# Quad_ESC_controller.net
KiCad netlist of a schematic drawn in EAGLE
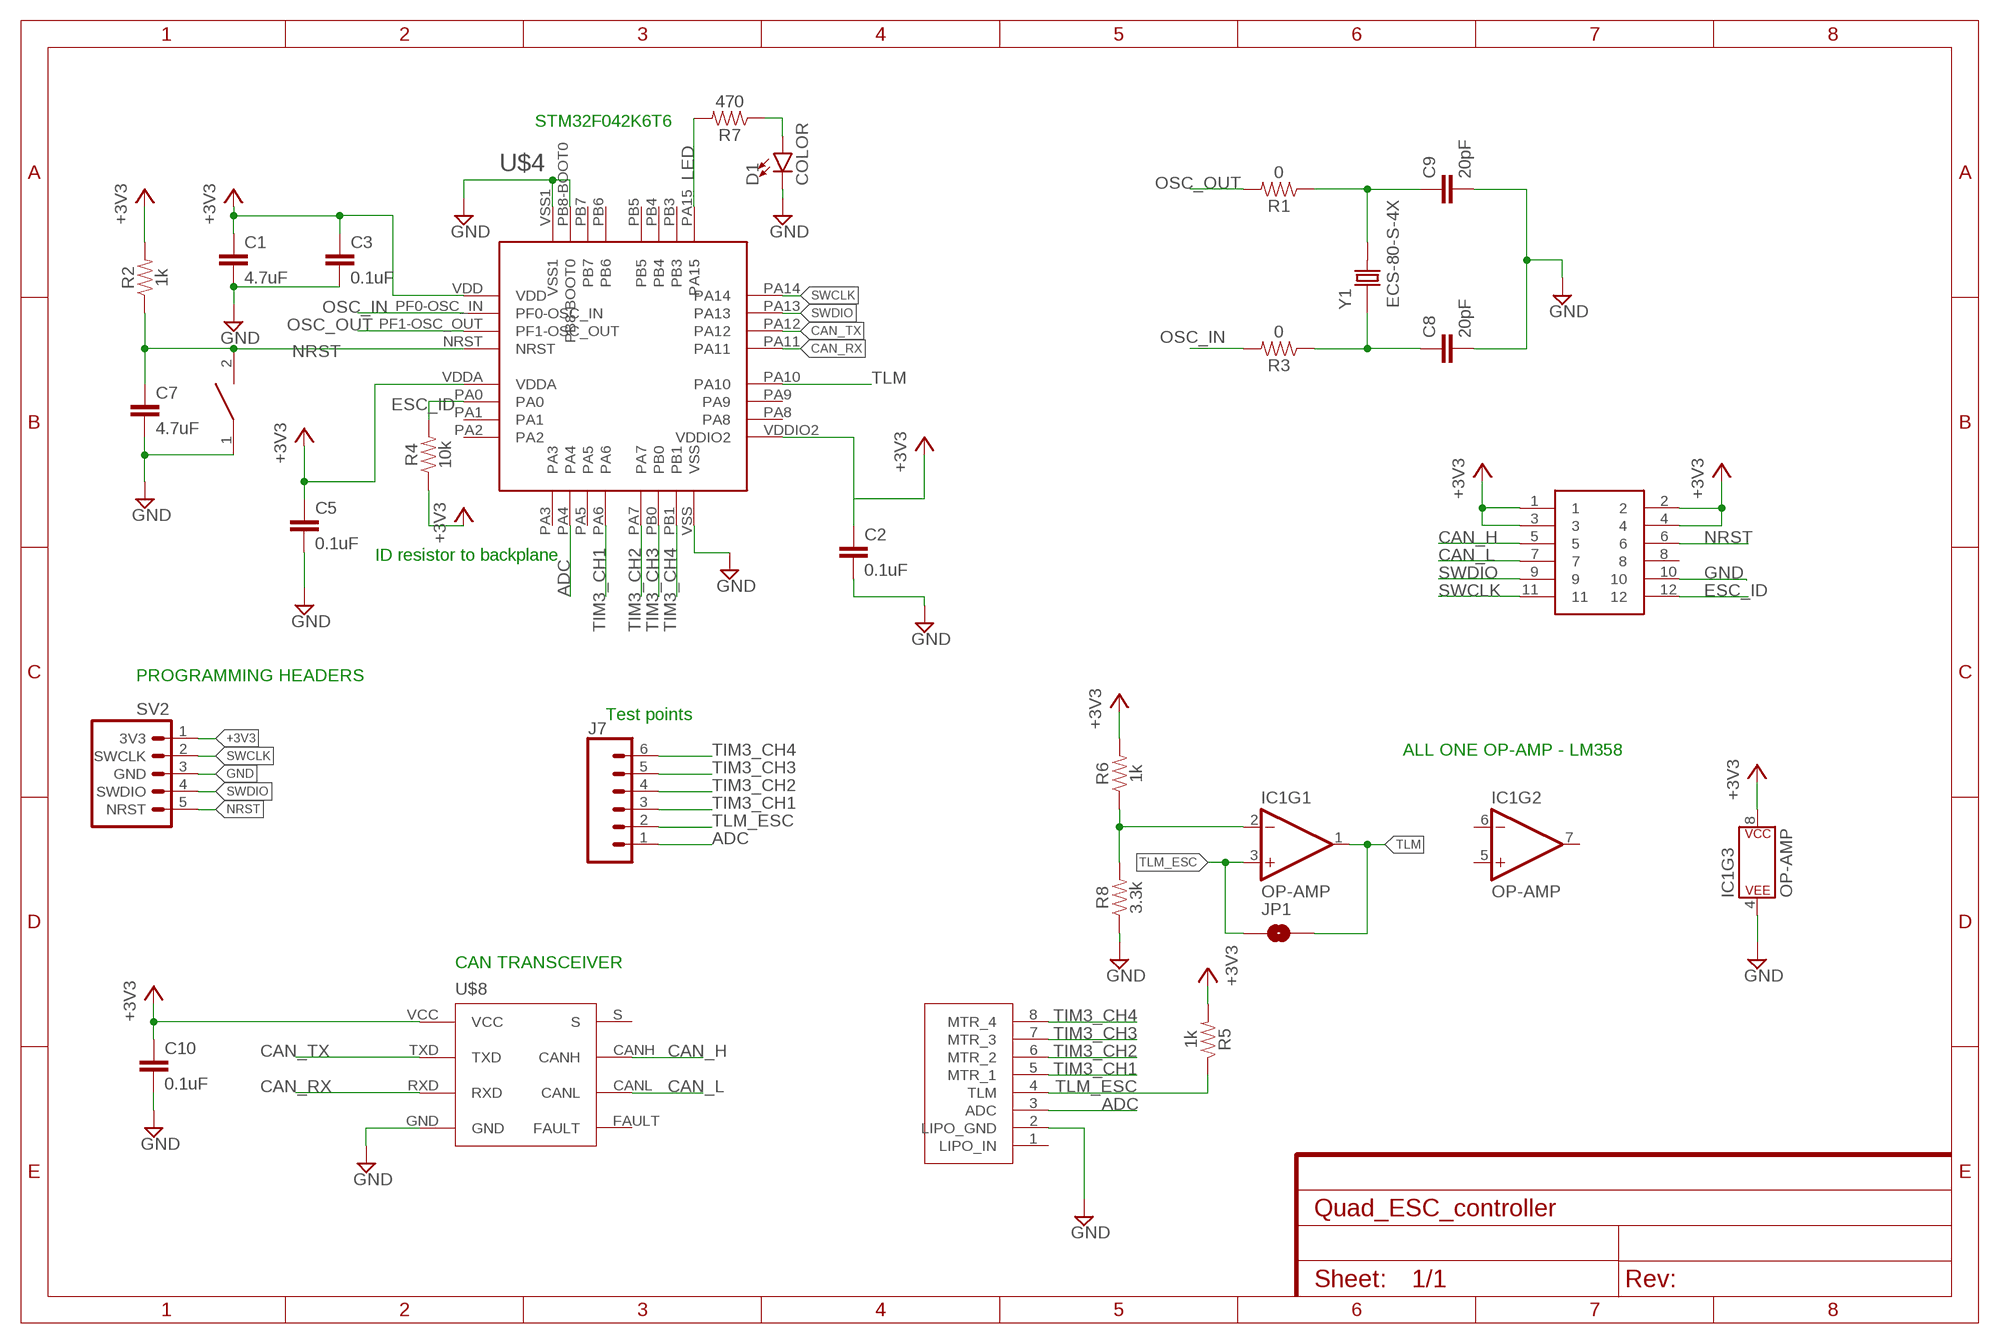
[diagram p0: schematic, sheet 1]

(export (version "E")
  (design (tool "Eeschema 10.0.6"))
  (components
    (comp (ref "C1")
      (value "4.7uF")
      (footprint "eagle-import:0603")
      (libsource (lib "eagle-import") (part "4.7UF0603"))
    )
    (comp (ref "C2")
      (value "0.1uF")
      (footprint "eagle-import:0603")
      (libsource (lib "eagle-import") (part "4.7UF0603"))
    )
    (comp (ref "C3")
      (value "0.1uF")
      (footprint "eagle-import:0603")
      (libsource (lib "eagle-import") (part "4.7UF0603"))
    )
    (comp (ref "C5")
      (value "0.1uF")
      (footprint "eagle-import:0603")
      (libsource (lib "eagle-import") (part "4.7UF0603"))
    )
    (comp (ref "C7")
      (value "4.7uF")
      (footprint "eagle-import:0603")
      (libsource (lib "eagle-import") (part "4.7UF0603"))
    )
    (comp (ref "C8")
      (value "20pF")
      (footprint "eagle-import:0603")
      (libsource (lib "eagle-import") (part "4.7UF0603"))
    )
    (comp (ref "C9")
      (value "20pF")
      (footprint "eagle-import:0603")
      (libsource (lib "eagle-import") (part "4.7UF0603"))
    )
    (comp (ref "C10")
      (value "0.1uF")
      (footprint "eagle-import:0603")
      (libsource (lib "eagle-import") (part "4.7UF0603"))
    )
    (comp (ref "D1")
      (value "COLOR")
      (footprint "eagle-import:0805")
      (libsource (lib "eagle-import") (part "LED-0805"))
    )
    (comp (ref "IC1")
      (value "OP-AMP")
      (footprint "eagle-import:SO08")
      (libsource (lib "eagle-import") (part "OPAMP-DUALU"))
    )
    (comp (ref "J7")
      (value "CONN_06SILK_FEMALE_PTH")
      (footprint "eagle-import:1X06")
      (libsource (lib "eagle-import") (part "CONN_06SILK_FEMALE_PTH"))
    )
    (comp (ref "JP1")
      (value "JUMPER-SMT_2_NO_SILK")
      (footprint "eagle-import:SMT-JUMPER_2_NO_SILK")
      (libsource (lib "eagle-import") (part "JUMPER-SMT_2_NO_SILK"))
    )
    (comp (ref "R1")
      (value "0")
      (footprint "eagle-import:0603")
      (libsource (lib "eagle-import") (part "1KOHM-0603-1/10W-1%"))
    )
    (comp (ref "R2")
      (value "1k")
      (footprint "eagle-import:0603")
      (libsource (lib "eagle-import") (part "1KOHM-0603-1/10W-1%"))
    )
    (comp (ref "R3")
      (value "0")
      (footprint "eagle-import:0603")
      (libsource (lib "eagle-import") (part "1KOHM-0603-1/10W-1%"))
    )
    (comp (ref "R4")
      (value "10k")
      (footprint "eagle-import:0603")
      (libsource (lib "eagle-import") (part "10KOHM-0603-1/10W-1%"))
    )
    (comp (ref "R5")
      (value "1k")
      (footprint "eagle-import:0603")
      (libsource (lib "eagle-import") (part "RESISTOR0603"))
    )
    (comp (ref "R6")
      (value "1k")
      (footprint "eagle-import:0603")
      (libsource (lib "eagle-import") (part "RESISTOR0603"))
    )
    (comp (ref "R7")
      (value "470")
      (footprint "eagle-import:0603")
      (libsource (lib "eagle-import") (part "RESISTOR0603"))
    )
    (comp (ref "R8")
      (value "3.3k")
      (footprint "eagle-import:0603")
      (libsource (lib "eagle-import") (part "RESISTOR0603"))
    )
    (comp (ref "RESET")
      (value "DISCRETECOMPONENTS_SWITCH")
      (footprint "eagle-import:DISCRETECOMPONENTS_SW_2512")
      (libsource (lib "eagle-import") (part "DISCRETECOMPONENTS_SWITCH"))
    )
    (comp (ref "SV2")
      (value "3V3 -SWCLK-GND-SWDIO- NRST")
      (footprint "eagle-import:1X05")
      (libsource (lib "eagle-import") (part "SWD_CONN"))
    )
    (comp (ref "U$2")
      (value "JST-8PIN")
      (footprint "eagle-import:8PIN_CONNECTOR")
      (libsource (lib "eagle-import") (part "JST-8PIN"))
    )
    (comp (ref "U$3")
      (value "BACKPLANE_CONNECTORSESC")
      (footprint "eagle-import:BACKPLANE_CONNECTORS_ESC")
      (libsource (lib "eagle-import") (part "BACKPLANE_CONNECTORSESC"))
    )
    (comp (ref "U$4")
      (value "STM32F042K6T6")
      (footprint "eagle-import:STM32F042K6T6")
      (libsource (lib "eagle-import") (part "STM32F042K6T6"))
    )
    (comp (ref "U$8")
      (value "TCAN337D")
      (footprint "eagle-import:TCAN337D")
      (libsource (lib "eagle-import") (part "TCAN337D"))
    )
    (comp (ref "Y1")
      (value "ECS-80-S-4X")
      (footprint "eagle-import:XTAL_ECS-80-S-4X")
      (fields (field (name "DIGI-KEY_PART_NUMBER") "X1057-ND") (field (name "MF") "ECS International"))
      (libsource (lib "eagle-import") (part "ECS-80-S-4X"))
    )
  )
  (nets
    (net (code "1") (name "+3V3") (class "Default")
      (node (ref "C1") (pin "1") (pinfunction "1_1") (pintype "passive"))
      (node (ref "C10") (pin "1") (pinfunction "1_1") (pintype "passive"))
      (node (ref "C2") (pin "1") (pinfunction "1_1") (pintype "passive"))
      (node (ref "C3") (pin "1") (pinfunction "1_1") (pintype "passive"))
      (node (ref "C5") (pin "1") (pinfunction "1_1") (pintype "passive"))
      (node (ref "IC1") (pin "8") (pinfunction "P$V+_8") (pintype "bidirectional"))
      (node (ref "R2") (pin "2") (pinfunction "2_2") (pintype "passive"))
      (node (ref "R4") (pin "1") (pinfunction "1_1") (pintype "passive"))
      (node (ref "R5") (pin "2") (pinfunction "2_2") (pintype "passive"))
      (node (ref "R6") (pin "2") (pinfunction "2_2") (pintype "passive"))
      (node (ref "SV2") (pin "1") (pinfunction "3V3_1") (pintype "power_in"))
      (node (ref "U$3") (pin "1") (pinfunction "1_1") (pintype "passive"))
      (node (ref "U$3") (pin "2") (pinfunction "2_2") (pintype "passive"))
      (node (ref "U$3") (pin "3") (pinfunction "3_3") (pintype "passive"))
      (node (ref "U$3") (pin "4") (pinfunction "4_4") (pintype "passive"))
      (node (ref "U$4") (pin "VDD") (pinfunction "VDD_VDD") (pintype "bidirectional"))
      (node (ref "U$4") (pin "VDDA") (pinfunction "VDDA_VDDA") (pintype "bidirectional"))
      (node (ref "U$4") (pin "VDDIO2") (pinfunction "VDDIO2_VDDIO2") (pintype "bidirectional"))
      (node (ref "U$8") (pin "VCC") (pinfunction "VCC_VCC") (pintype "bidirectional"))
    )
    (net (code "2") (name "/ADC") (class "Default")
      (node (ref "J7") (pin "1") (pinfunction "1_1") (pintype "passive"))
      (node (ref "U$2") (pin "3") (pinfunction "ADC_3") (pintype "bidirectional"))
      (node (ref "U$4") (pin "PA4") (pinfunction "PA4_PA4") (pintype "bidirectional"))
    )
    (net (code "3") (name "/CAN_H") (class "Default")
      (node (ref "U$3") (pin "5") (pinfunction "5_5") (pintype "passive"))
      (node (ref "U$8") (pin "CANH") (pinfunction "CANH_CANH") (pintype "bidirectional"))
    )
    (net (code "4") (name "/CAN_L") (class "Default")
      (node (ref "U$3") (pin "7") (pinfunction "7_7") (pintype "passive"))
      (node (ref "U$8") (pin "CANL") (pinfunction "CANL_CANL") (pintype "bidirectional"))
    )
    (net (code "5") (name "/ESC_ID") (class "Default")
      (node (ref "R4") (pin "2") (pinfunction "2_2") (pintype "passive"))
      (node (ref "U$3") (pin "12") (pinfunction "12_12") (pintype "passive"))
      (node (ref "U$4") (pin "PA0") (pinfunction "PA0_PA0") (pintype "bidirectional"))
    )
    (net (code "6") (name "/LED") (class "Default")
      (node (ref "R7") (pin "2") (pinfunction "2_2") (pintype "passive"))
      (node (ref "U$4") (pin "PA15") (pinfunction "PA15_PA15") (pintype "bidirectional"))
    )
    (net (code "7") (name "/OSC_IN") (class "Default")
      (node (ref "R3") (pin "2") (pinfunction "2_2") (pintype "passive"))
      (node (ref "U$4") (pin "PF0-OSC_IN") (pinfunction "PF0-OSC_IN_PF0-OSC_IN") (pintype "bidirectional"))
    )
    (net (code "8") (name "/OSC_OUT") (class "Default")
      (node (ref "R1") (pin "2") (pinfunction "2_2") (pintype "passive"))
      (node (ref "U$4") (pin "PF1-OSC_OUT") (pinfunction "PF1-OSC_OUT_PF1-OSC_OUT") (pintype "bidirectional"))
    )
    (net (code "9") (name "/TIM3_CH1") (class "Default")
      (node (ref "J7") (pin "3") (pinfunction "3_3") (pintype "passive"))
      (node (ref "U$2") (pin "5") (pinfunction "MTR_1_5") (pintype "bidirectional"))
      (node (ref "U$4") (pin "PA6") (pinfunction "PA6_PA6") (pintype "bidirectional"))
    )
    (net (code "10") (name "/TIM3_CH2") (class "Default")
      (node (ref "J7") (pin "4") (pinfunction "4_4") (pintype "passive"))
      (node (ref "U$2") (pin "6") (pinfunction "MTR_2_6") (pintype "bidirectional"))
      (node (ref "U$4") (pin "PA7") (pinfunction "PA7_PA7") (pintype "bidirectional"))
    )
    (net (code "11") (name "/TIM3_CH3") (class "Default")
      (node (ref "J7") (pin "5") (pinfunction "5_5") (pintype "passive"))
      (node (ref "U$2") (pin "7") (pinfunction "MTR_3_7") (pintype "bidirectional"))
      (node (ref "U$4") (pin "PB0") (pinfunction "PB0_PB0") (pintype "bidirectional"))
    )
    (net (code "12") (name "/TIM3_CH4") (class "Default")
      (node (ref "J7") (pin "6") (pinfunction "6_6") (pintype "passive"))
      (node (ref "U$2") (pin "8") (pinfunction "MTR_4_8") (pintype "bidirectional"))
      (node (ref "U$4") (pin "PB1") (pinfunction "PB1_PB1") (pintype "bidirectional"))
    )
    (net (code "13") (name "CAN_RX") (class "Default")
      (node (ref "U$4") (pin "PA11") (pinfunction "PA11_PA11") (pintype "bidirectional"))
      (node (ref "U$8") (pin "RXD") (pinfunction "RXD_RXD") (pintype "bidirectional"))
    )
    (net (code "14") (name "CAN_TX") (class "Default")
      (node (ref "U$4") (pin "PA12") (pinfunction "PA12_PA12") (pintype "bidirectional"))
      (node (ref "U$8") (pin "TXD") (pinfunction "TXD_TXD") (pintype "bidirectional"))
    )
    (net (code "15") (name "GND") (class "Default")
      (node (ref "C1") (pin "2") (pinfunction "2_2") (pintype "passive"))
      (node (ref "C10") (pin "2") (pinfunction "2_2") (pintype "passive"))
      (node (ref "C2") (pin "2") (pinfunction "2_2") (pintype "passive"))
      (node (ref "C3") (pin "2") (pinfunction "2_2") (pintype "passive"))
      (node (ref "C5") (pin "2") (pinfunction "2_2") (pintype "passive"))
      (node (ref "C7") (pin "2") (pinfunction "2_2") (pintype "passive"))
      (node (ref "C8") (pin "2") (pinfunction "2_2") (pintype "passive"))
      (node (ref "C9") (pin "2") (pinfunction "2_2") (pintype "passive"))
      (node (ref "D1") (pin "C") (pinfunction "C_C") (pintype "passive"))
      (node (ref "IC1") (pin "4") (pinfunction "P$V-_4") (pintype "bidirectional"))
      (node (ref "R8") (pin "1") (pinfunction "1_1") (pintype "passive"))
      (node (ref "RESET") (pin "1") (pinfunction "P$1_1") (pintype "bidirectional"))
      (node (ref "SV2") (pin "3") (pinfunction "GND_3") (pintype "power_in"))
      (node (ref "U$2") (pin "2") (pinfunction "LIPO_GND_2") (pintype "bidirectional"))
      (node (ref "U$3") (pin "10") (pinfunction "10_10") (pintype "passive"))
      (node (ref "U$4") (pin "PB8-BOOT0") (pinfunction "PB8-BOOT0_PB8-BOOT0") (pintype "bidirectional"))
      (node (ref "U$4") (pin "VSS") (pinfunction "VSS_VSS") (pintype "bidirectional"))
      (node (ref "U$4") (pin "VSS1") (pinfunction "VSS1_VSS1") (pintype "bidirectional"))
      (node (ref "U$8") (pin "GND") (pinfunction "GND_GND") (pintype "bidirectional"))
    )
    (net (code "16") (name "NRST") (class "Default")
      (node (ref "C7") (pin "1") (pinfunction "1_1") (pintype "passive"))
      (node (ref "R2") (pin "1") (pinfunction "1_1") (pintype "passive"))
      (node (ref "RESET") (pin "2") (pinfunction "P$2_2") (pintype "bidirectional"))
      (node (ref "SV2") (pin "5") (pinfunction "NRST_5") (pintype "open_collector"))
      (node (ref "U$3") (pin "6") (pinfunction "6_6") (pintype "passive"))
      (node (ref "U$4") (pin "NRST") (pinfunction "NRST_NRST") (pintype "bidirectional"))
    )
    (net (code "17") (name "Net-(C8-Pad1)") (class "Default")
      (node (ref "C8") (pin "1") (pinfunction "1_1") (pintype "passive"))
      (node (ref "R3") (pin "1") (pinfunction "1_1") (pintype "passive"))
      (node (ref "Y1") (pin "1") (pinfunction "1_1") (pintype "passive"))
    )
    (net (code "18") (name "Net-(C9-Pad1)") (class "Default")
      (node (ref "C9") (pin "1") (pinfunction "1_1") (pintype "passive"))
      (node (ref "R1") (pin "1") (pinfunction "1_1") (pintype "passive"))
      (node (ref "Y1") (pin "2") (pinfunction "2_2") (pintype "passive"))
    )
    (net (code "19") (name "Net-(D1-PadA)") (class "Default")
      (node (ref "D1") (pin "A") (pinfunction "A_A") (pintype "passive"))
      (node (ref "R7") (pin "1") (pinfunction "1_1") (pintype "passive"))
    )
    (net (code "20") (name "Net-(IC1A--IN)") (class "Default")
      (node (ref "IC1") (pin "2") (pinfunction "-IN_2") (pintype "input"))
      (node (ref "R6") (pin "1") (pinfunction "1_1") (pintype "passive"))
      (node (ref "R8") (pin "2") (pinfunction "2_2") (pintype "passive"))
    )
    (net (code "21") (name "SWCLK") (class "Default")
      (node (ref "SV2") (pin "2") (pinfunction "SWCLK_2") (pintype "input"))
      (node (ref "U$3") (pin "11") (pinfunction "11_11") (pintype "passive"))
      (node (ref "U$4") (pin "PA14") (pinfunction "PA14_PA14") (pintype "bidirectional"))
    )
    (net (code "22") (name "SWDIO") (class "Default")
      (node (ref "SV2") (pin "4") (pinfunction "SWDIO_4") (pintype "bidirectional"))
      (node (ref "U$3") (pin "9") (pinfunction "9_9") (pintype "passive"))
      (node (ref "U$4") (pin "PA13") (pinfunction "PA13_PA13") (pintype "bidirectional"))
    )
    (net (code "23") (name "TLM") (class "Default")
      (node (ref "IC1") (pin "1") (pinfunction "OUT_1") (pintype "output"))
      (node (ref "JP1") (pin "2") (pinfunction "2_2") (pintype "passive"))
      (node (ref "U$4") (pin "PA10") (pinfunction "PA10_PA10") (pintype "bidirectional"))
    )
    (net (code "24") (name "TLM_ESC") (class "Default")
      (node (ref "IC1") (pin "3") (pinfunction "+IN_3") (pintype "input"))
      (node (ref "J7") (pin "2") (pinfunction "2_2") (pintype "passive"))
      (node (ref "JP1") (pin "1") (pinfunction "1_1") (pintype "passive"))
      (node (ref "R5") (pin "1") (pinfunction "1_1") (pintype "passive"))
      (node (ref "U$2") (pin "4") (pinfunction "TLM_4") (pintype "bidirectional"))
    )
    (net (code "25") (name "unconnected-(IC1B-+IN-Pad5)") (class "Default")
      (node (ref "IC1") (pin "5") (pinfunction "+IN_5") (pintype "input"))
    )
    (net (code "26") (name "unconnected-(IC1B--IN-Pad6)") (class "Default")
      (node (ref "IC1") (pin "6") (pinfunction "-IN_6") (pintype "input"))
    )
    (net (code "27") (name "unconnected-(IC1B-OUT-Pad7)") (class "Default")
      (node (ref "IC1") (pin "7") (pinfunction "OUT_7") (pintype "output"))
    )
    (net (code "28") (name "unconnected-(U$2-LIPO_IN-Pad1)") (class "Default")
      (node (ref "U$2") (pin "1") (pinfunction "LIPO_IN_1") (pintype "bidirectional"))
    )
    (net (code "29") (name "unconnected-(U$3-Pad8)") (class "Default")
      (node (ref "U$3") (pin "8") (pinfunction "8_8") (pintype "passive"))
    )
    (net (code "30") (name "unconnected-(U$4-PadPA1)") (class "Default")
      (node (ref "U$4") (pin "PA1") (pinfunction "PA1_PA1") (pintype "bidirectional"))
    )
    (net (code "31") (name "unconnected-(U$4-PadPA2)") (class "Default")
      (node (ref "U$4") (pin "PA2") (pinfunction "PA2_PA2") (pintype "bidirectional"))
    )
    (net (code "32") (name "unconnected-(U$4-PadPA3)") (class "Default")
      (node (ref "U$4") (pin "PA3") (pinfunction "PA3_PA3") (pintype "bidirectional"))
    )
    (net (code "33") (name "unconnected-(U$4-PadPA5)") (class "Default")
      (node (ref "U$4") (pin "PA5") (pinfunction "PA5_PA5") (pintype "bidirectional"))
    )
    (net (code "34") (name "unconnected-(U$4-PadPA8)") (class "Default")
      (node (ref "U$4") (pin "PA8") (pinfunction "PA8_PA8") (pintype "bidirectional"))
    )
    (net (code "35") (name "unconnected-(U$4-PadPA9)") (class "Default")
      (node (ref "U$4") (pin "PA9") (pinfunction "PA9_PA9") (pintype "bidirectional"))
    )
    (net (code "36") (name "unconnected-(U$4-PadPB3)") (class "Default")
      (node (ref "U$4") (pin "PB3") (pinfunction "PB3_PB3") (pintype "bidirectional"))
    )
    (net (code "37") (name "unconnected-(U$4-PadPB4)") (class "Default")
      (node (ref "U$4") (pin "PB4") (pinfunction "PB4_PB4") (pintype "bidirectional"))
    )
    (net (code "38") (name "unconnected-(U$4-PadPB5)") (class "Default")
      (node (ref "U$4") (pin "PB5") (pinfunction "PB5_PB5") (pintype "bidirectional"))
    )
    (net (code "39") (name "unconnected-(U$4-PadPB6)") (class "Default")
      (node (ref "U$4") (pin "PB6") (pinfunction "PB6_PB6") (pintype "bidirectional"))
    )
    (net (code "40") (name "unconnected-(U$4-PadPB7)") (class "Default")
      (node (ref "U$4") (pin "PB7") (pinfunction "PB7_PB7") (pintype "bidirectional"))
    )
    (net (code "41") (name "unconnected-(U$8-PadFAULT)") (class "Default")
      (node (ref "U$8") (pin "FAULT") (pinfunction "FAULT_FAULT") (pintype "bidirectional"))
    )
    (net (code "42") (name "unconnected-(U$8-PadS)") (class "Default")
      (node (ref "U$8") (pin "S") (pinfunction "S_S") (pintype "bidirectional"))
    )
  )
)
